# siu-clock-breakout.net
KiCad netlist of a schematic drawn in EAGLE
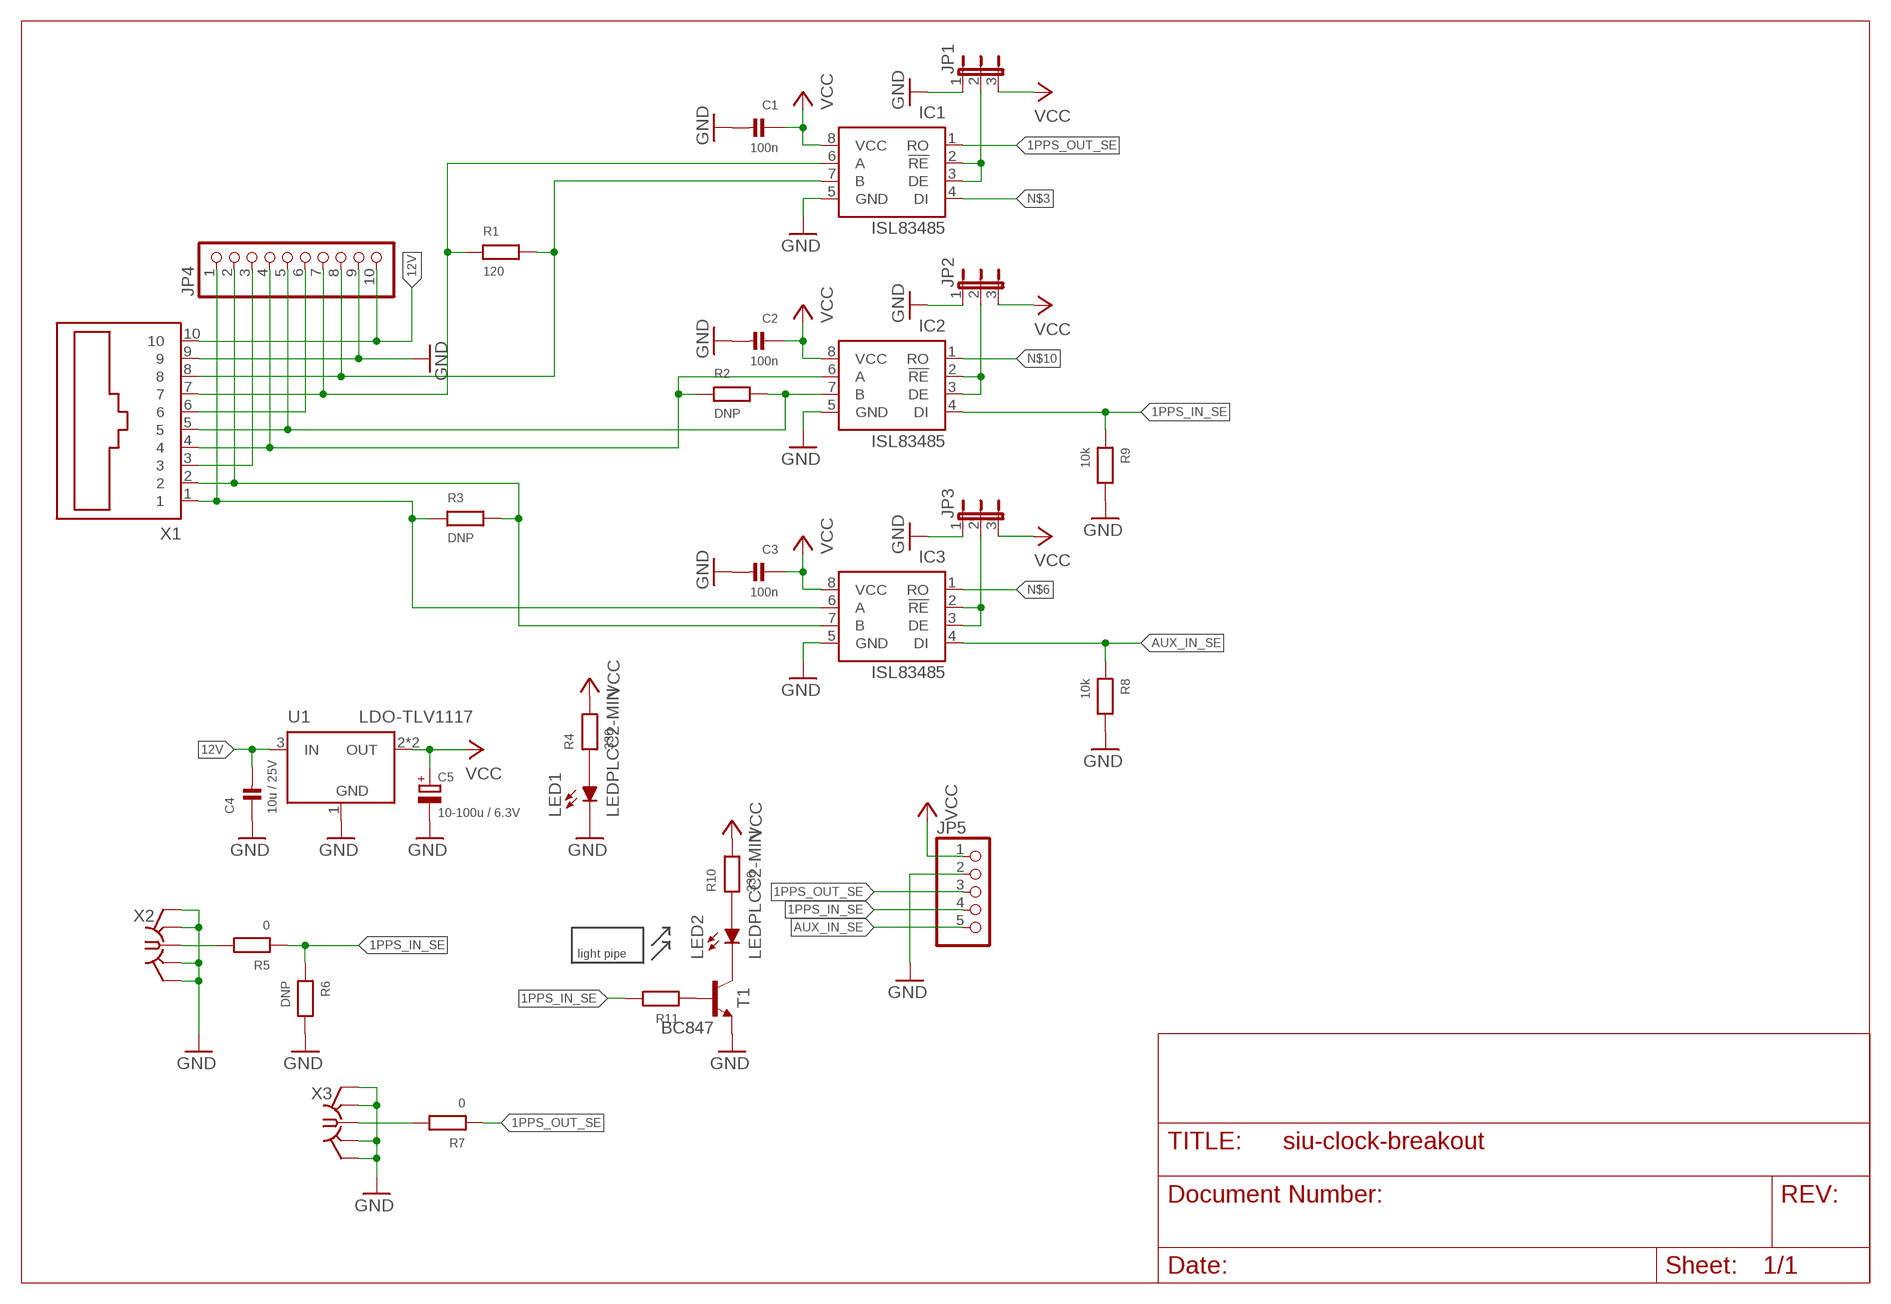
[diagram p0: schematic, sheet 1]

(export (version "E")
  (design (tool "Eeschema 10.0.6"))
  (components
    (comp (ref "C1")
      (value "100n")
      (footprint "eagle-import:_0603")
      (libsource (lib "eagle-import") (part "CAP_CERAMIC_0603"))
    )
    (comp (ref "C2")
      (value "100n")
      (footprint "eagle-import:_0603")
      (libsource (lib "eagle-import") (part "CAP_CERAMIC_0603"))
    )
    (comp (ref "C3")
      (value "100n")
      (footprint "eagle-import:_0603")
      (libsource (lib "eagle-import") (part "CAP_CERAMIC_0603"))
    )
    (comp (ref "C4")
      (value "10u / 25V")
      (footprint "eagle-import:_0805")
      (libsource (lib "eagle-import") (part "CAP_CERAMIC_0805"))
    )
    (comp (ref "C5")
      (value "10-100u / 6.3V")
      (footprint "eagle-import:CPOL1206")
      (libsource (lib "eagle-import") (part "CPOL-EU-1206"))
    )
    (comp (ref "IC1")
      (value "ISL83485")
      (footprint "eagle-import:SOIC8")
      (libsource (lib "eagle-import") (part "LTC485S"))
    )
    (comp (ref "IC2")
      (value "ISL83485")
      (footprint "eagle-import:SOIC8")
      (libsource (lib "eagle-import") (part "LTC485S"))
    )
    (comp (ref "IC3")
      (value "ISL83485")
      (footprint "eagle-import:SOIC8")
      (libsource (lib "eagle-import") (part "LTC485S"))
    )
    (comp (ref "JP1")
      (value "JP2E")
      (footprint "eagle-import:JP2")
      (libsource (lib "eagle-import") (part "JP2E"))
    )
    (comp (ref "JP2")
      (value "JP2E")
      (footprint "eagle-import:JP2")
      (libsource (lib "eagle-import") (part "JP2E"))
    )
    (comp (ref "JP3")
      (value "JP2E")
      (footprint "eagle-import:JP2")
      (libsource (lib "eagle-import") (part "JP2E"))
    )
    (comp (ref "JP4")
      (value "PINHD-1X10")
      (footprint "eagle-import:1X10")
      (libsource (lib "eagle-import") (part "PINHD-1X10"))
    )
    (comp (ref "JP5")
      (value "PINHD-1X5")
      (footprint "eagle-import:1X05")
      (libsource (lib "eagle-import") (part "PINHD-1X5"))
    )
    (comp (ref "LED1")
      (value "LEDPLCC2-MIN")
      (footprint "eagle-import:PLCC2-MIN")
      (libsource (lib "eagle-import") (part "LEDPLCC2-MIN"))
    )
    (comp (ref "LED2")
      (value "LEDPLCC2-MIN")
      (footprint "eagle-import:PLCC2-MIN")
      (libsource (lib "eagle-import") (part "LEDPLCC2-MIN"))
    )
    (comp (ref "M1")
      (value "MENTOR_12701001")
      (footprint "eagle-import:1270.1001")
      (libsource (lib "eagle-import") (part "MENTOR_12701001"))
    )
    (comp (ref "R1")
      (value "120")
      (footprint "eagle-import:_0805")
      (libsource (lib "eagle-import") (part "RESISTOR_0805"))
    )
    (comp (ref "R2")
      (value "DNP")
      (footprint "eagle-import:_0805")
      (libsource (lib "eagle-import") (part "RESISTOR_0805"))
    )
    (comp (ref "R3")
      (value "DNP")
      (footprint "eagle-import:_0805")
      (libsource (lib "eagle-import") (part "RESISTOR_0805"))
    )
    (comp (ref "R4")
      (value "330")
      (footprint "eagle-import:_0603")
      (libsource (lib "eagle-import") (part "RESISTOR_0603"))
    )
    (comp (ref "R5")
      (value "0")
      (footprint "eagle-import:_0603")
      (libsource (lib "eagle-import") (part "RESISTOR_0603"))
    )
    (comp (ref "R6")
      (value "DNP")
      (footprint "eagle-import:_0603")
      (libsource (lib "eagle-import") (part "RESISTOR_0603"))
    )
    (comp (ref "R7")
      (value "0")
      (footprint "eagle-import:_0603")
      (libsource (lib "eagle-import") (part "RESISTOR_0603"))
    )
    (comp (ref "R8")
      (value "10k")
      (footprint "eagle-import:_0603")
      (libsource (lib "eagle-import") (part "RESISTOR_0603"))
    )
    (comp (ref "R9")
      (value "10k")
      (footprint "eagle-import:_0603")
      (libsource (lib "eagle-import") (part "RESISTOR_0603"))
    )
    (comp (ref "R10")
      (value "330")
      (footprint "eagle-import:_0603")
      (libsource (lib "eagle-import") (part "RESISTOR_0603"))
    )
    (comp (ref "R11")
      (value "RESISTOR_0603")
      (footprint "eagle-import:_0603")
      (libsource (lib "eagle-import") (part "RESISTOR_0603"))
    )
    (comp (ref "T1")
      (value "BC847")
      (footprint "eagle-import:SOT23-BEC")
      (description "TRANS NPN 45V 0.1A SOT23")
      (fields
        (field (name "MANUFACTURER") "Nexperia USA Inc.")
        (field (name "MANUFACTURERPARTNUMBER") "BC847C,215")
      )
      (libsource (lib "eagle-import") (part "-NPN-SOT23-BECBC847C"))
    )
    (comp (ref "U1")
      (value "LDO-TLV1117")
      (footprint "eagle-import:SOT223")
      (libsource (lib "eagle-import") (part "LDO-TLV1117"))
    )
    (comp (ref "X1")
      (value "RJ45-10P10C-SS-641010-NF")
      (footprint "eagle-import:SS-641010-NF")
      (libsource (lib "eagle-import") (part "RJ45-10P10C-SS-641010-NF"))
    )
    (comp (ref "X2")
      (value "SMA-F-S-TH")
      (footprint "eagle-import:SMA-F-S-TH")
      (libsource (lib "eagle-import") (part "SMA-F-S-TH"))
    )
    (comp (ref "X3")
      (value "SMA-F-S-TH")
      (footprint "eagle-import:SMA-F-S-TH")
      (libsource (lib "eagle-import") (part "SMA-F-S-TH"))
    )
  )
  (nets
    (net (code "1") (name "1PPS_IN_SE") (class "Default")
      (node (ref "IC2") (pin "4") (pinfunction "DI_4") (pintype "input"))
      (node (ref "JP5") (pin "4") (pinfunction "4_4") (pintype "passive"))
      (node (ref "R11") (pin "2") (pinfunction "2_2") (pintype "passive"))
      (node (ref "R5") (pin "1") (pinfunction "1_1") (pintype "passive"))
      (node (ref "R6") (pin "1") (pinfunction "1_1") (pintype "passive"))
      (node (ref "R9") (pin "1") (pinfunction "1_1") (pintype "passive"))
    )
    (net (code "2") (name "1PPS_OUT_SE") (class "Default")
      (node (ref "IC1") (pin "1") (pinfunction "RO_1") (pintype "output"))
      (node (ref "JP5") (pin "3") (pinfunction "3_3") (pintype "passive"))
      (node (ref "R7") (pin "1") (pinfunction "1_1") (pintype "passive"))
    )
    (net (code "3") (name "12V") (class "Default")
      (node (ref "C4") (pin "2") (pinfunction "2_2") (pintype "passive"))
      (node (ref "JP4") (pin "10") (pinfunction "10_10") (pintype "passive"))
      (node (ref "U1") (pin "3") (pinfunction "IN_3") (pintype "input"))
      (node (ref "X1") (pin "10") (pinfunction "10_10") (pintype "passive"))
    )
    (net (code "4") (name "AUX_IN_SE") (class "Default")
      (node (ref "IC3") (pin "4") (pinfunction "DI_4") (pintype "input"))
      (node (ref "JP5") (pin "5") (pinfunction "5_5") (pintype "passive"))
      (node (ref "R8") (pin "1") (pinfunction "1_1") (pintype "passive"))
    )
    (net (code "5") (name "GND") (class "Default")
      (node (ref "C1") (pin "2") (pinfunction "2_2") (pintype "passive"))
      (node (ref "C2") (pin "2") (pinfunction "2_2") (pintype "passive"))
      (node (ref "C3") (pin "2") (pinfunction "2_2") (pintype "passive"))
      (node (ref "C4") (pin "1") (pinfunction "1_1") (pintype "passive"))
      (node (ref "C5") (pin "-") (pinfunction "-_-") (pintype "passive"))
      (node (ref "IC1") (pin "5") (pinfunction "GND_5") (pintype "input"))
      (node (ref "IC2") (pin "5") (pinfunction "GND_5") (pintype "input"))
      (node (ref "IC3") (pin "5") (pinfunction "GND_5") (pintype "input"))
      (node (ref "JP1") (pin "1") (pinfunction "1_1") (pintype "passive"))
      (node (ref "JP2") (pin "1") (pinfunction "1_1") (pintype "passive"))
      (node (ref "JP3") (pin "1") (pinfunction "1_1") (pintype "passive"))
      (node (ref "JP4") (pin "9") (pinfunction "9_9") (pintype "passive"))
      (node (ref "JP5") (pin "2") (pinfunction "2_2") (pintype "passive"))
      (node (ref "LED1") (pin "K") (pinfunction "C_K") (pintype "passive"))
      (node (ref "R6") (pin "2") (pinfunction "2_2") (pintype "passive"))
      (node (ref "R8") (pin "2") (pinfunction "2_2") (pintype "passive"))
      (node (ref "R9") (pin "2") (pinfunction "2_2") (pintype "passive"))
      (node (ref "T1") (pin "E") (pinfunction "E_E") (pintype "passive"))
      (node (ref "U1") (pin "1") (pinfunction "GND_1") (pintype "power_in"))
      (node (ref "X1") (pin "9") (pinfunction "9_9") (pintype "passive"))
      (node (ref "X2") (pin "G1") (pinfunction "GND_G1") (pintype "power_in"))
      (node (ref "X2") (pin "G2") (pinfunction "GND_G2") (pintype "power_in"))
      (node (ref "X2") (pin "G3") (pinfunction "GND_G3") (pintype "power_in"))
      (node (ref "X2") (pin "G4") (pinfunction "GND_G4") (pintype "power_in"))
      (node (ref "X3") (pin "G1") (pinfunction "GND_G1") (pintype "power_in"))
      (node (ref "X3") (pin "G2") (pinfunction "GND_G2") (pintype "power_in"))
      (node (ref "X3") (pin "G3") (pinfunction "GND_G3") (pintype "power_in"))
      (node (ref "X3") (pin "G4") (pinfunction "GND_G4") (pintype "power_in"))
    )
    (net (code "6") (name "N$3") (class "Default")
      (node (ref "IC1") (pin "4") (pinfunction "DI_4") (pintype "input"))
    )
    (net (code "7") (name "N$6") (class "Default")
      (node (ref "IC3") (pin "1") (pinfunction "RO_1") (pintype "output"))
    )
    (net (code "8") (name "N$10") (class "Default")
      (node (ref "IC2") (pin "1") (pinfunction "RO_1") (pintype "output"))
    )
    (net (code "9") (name "Net-(IC1-A)") (class "Default")
      (node (ref "IC1") (pin "6") (pinfunction "A_6") (pintype "bidirectional"))
      (node (ref "JP4") (pin "7") (pinfunction "7_7") (pintype "passive"))
      (node (ref "R1") (pin "1") (pinfunction "1_1") (pintype "passive"))
      (node (ref "X1") (pin "7") (pinfunction "7_7") (pintype "passive"))
    )
    (net (code "10") (name "Net-(IC1-B)") (class "Default")
      (node (ref "IC1") (pin "7") (pinfunction "B_7") (pintype "bidirectional"))
      (node (ref "JP4") (pin "8") (pinfunction "8_8") (pintype "passive"))
      (node (ref "R1") (pin "2") (pinfunction "2_2") (pintype "passive"))
      (node (ref "X1") (pin "8") (pinfunction "8_8") (pintype "passive"))
    )
    (net (code "11") (name "Net-(IC1-DE)") (class "Default")
      (node (ref "IC1") (pin "2") (pinfunction "~{RE}_2") (pintype "input"))
      (node (ref "IC1") (pin "3") (pinfunction "DE_3") (pintype "input"))
      (node (ref "JP1") (pin "2") (pinfunction "2_2") (pintype "passive"))
    )
    (net (code "12") (name "Net-(IC2-A)") (class "Default")
      (node (ref "IC2") (pin "6") (pinfunction "A_6") (pintype "bidirectional"))
      (node (ref "JP4") (pin "4") (pinfunction "4_4") (pintype "passive"))
      (node (ref "R2") (pin "1") (pinfunction "1_1") (pintype "passive"))
      (node (ref "X1") (pin "4") (pinfunction "4_4") (pintype "passive"))
    )
    (net (code "13") (name "Net-(IC2-B)") (class "Default")
      (node (ref "IC2") (pin "7") (pinfunction "B_7") (pintype "bidirectional"))
      (node (ref "JP4") (pin "5") (pinfunction "5_5") (pintype "passive"))
      (node (ref "R2") (pin "2") (pinfunction "2_2") (pintype "passive"))
      (node (ref "X1") (pin "5") (pinfunction "5_5") (pintype "passive"))
    )
    (net (code "14") (name "Net-(IC2-DE)") (class "Default")
      (node (ref "IC2") (pin "2") (pinfunction "~{RE}_2") (pintype "input"))
      (node (ref "IC2") (pin "3") (pinfunction "DE_3") (pintype "input"))
      (node (ref "JP2") (pin "2") (pinfunction "2_2") (pintype "passive"))
    )
    (net (code "15") (name "Net-(IC3-A)") (class "Default")
      (node (ref "IC3") (pin "6") (pinfunction "A_6") (pintype "bidirectional"))
      (node (ref "JP4") (pin "1") (pinfunction "1_1") (pintype "passive"))
      (node (ref "R3") (pin "1") (pinfunction "1_1") (pintype "passive"))
      (node (ref "X1") (pin "1") (pinfunction "1_1") (pintype "passive"))
    )
    (net (code "16") (name "Net-(IC3-B)") (class "Default")
      (node (ref "IC3") (pin "7") (pinfunction "B_7") (pintype "bidirectional"))
      (node (ref "JP4") (pin "2") (pinfunction "2_2") (pintype "passive"))
      (node (ref "R3") (pin "2") (pinfunction "2_2") (pintype "passive"))
      (node (ref "X1") (pin "2") (pinfunction "2_2") (pintype "passive"))
    )
    (net (code "17") (name "Net-(IC3-DE)") (class "Default")
      (node (ref "IC3") (pin "2") (pinfunction "~{RE}_2") (pintype "input"))
      (node (ref "IC3") (pin "3") (pinfunction "DE_3") (pintype "input"))
      (node (ref "JP3") (pin "2") (pinfunction "2_2") (pintype "passive"))
    )
    (net (code "18") (name "Net-(JP4-Pad3)") (class "Default")
      (node (ref "JP4") (pin "3") (pinfunction "3_3") (pintype "passive"))
      (node (ref "X1") (pin "3") (pinfunction "3_3") (pintype "passive"))
    )
    (net (code "19") (name "Net-(JP4-Pad6)") (class "Default")
      (node (ref "JP4") (pin "6") (pinfunction "6_6") (pintype "passive"))
      (node (ref "X1") (pin "6") (pinfunction "6_6") (pintype "passive"))
    )
    (net (code "20") (name "Net-(LED1-PadA)") (class "Default")
      (node (ref "LED1") (pin "A") (pinfunction "A_A") (pintype "passive"))
      (node (ref "R4") (pin "1") (pinfunction "1_1") (pintype "passive"))
    )
    (net (code "21") (name "Net-(LED2-C)") (class "Default")
      (node (ref "LED2") (pin "K") (pinfunction "C_K") (pintype "passive"))
      (node (ref "T1") (pin "C") (pinfunction "C_C") (pintype "passive"))
    )
    (net (code "22") (name "Net-(LED2-PadA)") (class "Default")
      (node (ref "LED2") (pin "A") (pinfunction "A_A") (pintype "passive"))
      (node (ref "R10") (pin "1") (pinfunction "1_1") (pintype "passive"))
    )
    (net (code "23") (name "Net-(R11-Pad1)") (class "Default")
      (node (ref "R11") (pin "1") (pinfunction "1_1") (pintype "passive"))
      (node (ref "T1") (pin "B") (pinfunction "B_B") (pintype "passive"))
    )
    (net (code "24") (name "Net-(X2-1)") (class "Default")
      (node (ref "R5") (pin "2") (pinfunction "2_2") (pintype "passive"))
      (node (ref "X2") (pin "C") (pinfunction "1_C") (pintype "passive"))
    )
    (net (code "25") (name "Net-(X3-1)") (class "Default")
      (node (ref "R7") (pin "2") (pinfunction "2_2") (pintype "passive"))
      (node (ref "X3") (pin "C") (pinfunction "1_C") (pintype "passive"))
    )
    (net (code "26") (name "VCC") (class "Default")
      (node (ref "C1") (pin "1") (pinfunction "1_1") (pintype "passive"))
      (node (ref "C2") (pin "1") (pinfunction "1_1") (pintype "passive"))
      (node (ref "C3") (pin "1") (pinfunction "1_1") (pintype "passive"))
      (node (ref "C5") (pin "+") (pinfunction "+_+") (pintype "passive"))
      (node (ref "IC1") (pin "8") (pinfunction "VCC_8") (pintype "input"))
      (node (ref "IC2") (pin "8") (pinfunction "VCC_8") (pintype "input"))
      (node (ref "IC3") (pin "8") (pinfunction "VCC_8") (pintype "input"))
      (node (ref "JP1") (pin "3") (pinfunction "3_3") (pintype "passive"))
      (node (ref "JP2") (pin "3") (pinfunction "3_3") (pintype "passive"))
      (node (ref "JP3") (pin "3") (pinfunction "3_3") (pintype "passive"))
      (node (ref "JP5") (pin "1") (pinfunction "1_1") (pintype "passive"))
      (node (ref "R10") (pin "2") (pinfunction "2_2") (pintype "passive"))
      (node (ref "R4") (pin "2") (pinfunction "2_2") (pintype "passive"))
      (node (ref "U1") (pin "2") (pinfunction "OUT_2") (pintype "passive"))
      (node (ref "U1") (pin "4") (pinfunction "OUT_4") (pintype "passive"))
    )
  )
)
